# kugarem_nosilk.net
KiCad netlist of a schematic drawn in EAGLE
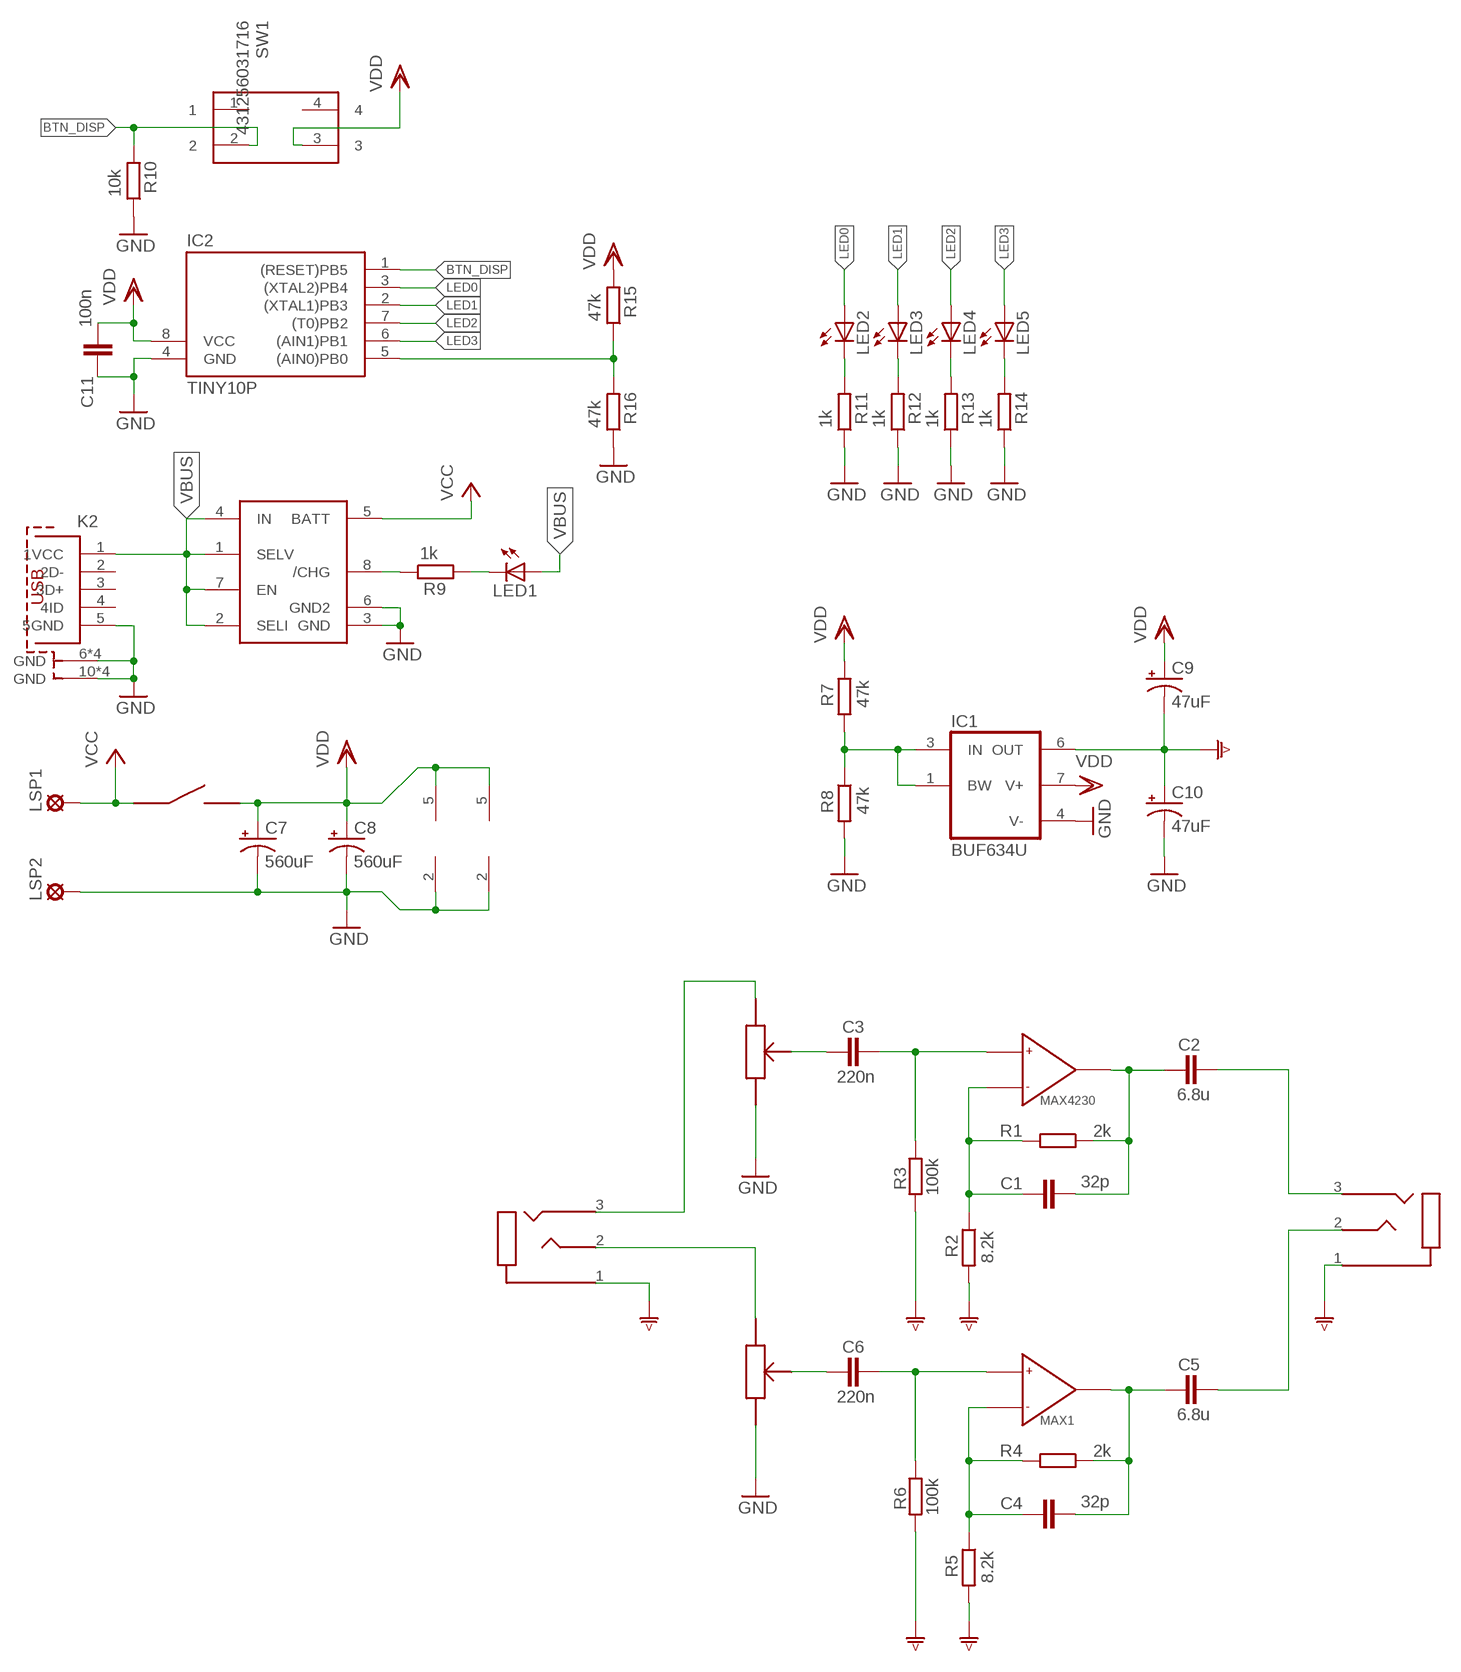
[diagram p0: schematic, sheet 1]

(export (version "E")
  (design (tool "Eeschema 10.0.6"))
  (components
    (comp (ref "C1")
      (value "32p")
      (footprint "eagle-import:C1206")
      (libsource (lib "eagle-import") (part "C-EUC1206"))
    )
    (comp (ref "C2")
      (value "6.8u")
      (footprint "eagle-import:C1206")
      (libsource (lib "eagle-import") (part "C-EUC1206"))
    )
    (comp (ref "C3")
      (value "220n")
      (footprint "eagle-import:C1206")
      (libsource (lib "eagle-import") (part "C-EUC1206"))
    )
    (comp (ref "C4")
      (value "32p")
      (footprint "eagle-import:C1206")
      (libsource (lib "eagle-import") (part "C-EUC1206"))
    )
    (comp (ref "C5")
      (value "6.8u")
      (footprint "eagle-import:C1206")
      (libsource (lib "eagle-import") (part "C-EUC1206"))
    )
    (comp (ref "C6")
      (value "220n")
      (footprint "eagle-import:C1206")
      (libsource (lib "eagle-import") (part "C-EUC1206"))
    )
    (comp (ref "C7")
      (value "560uF")
      (footprint "eagle-import:PANASONIC_G")
      (libsource (lib "eagle-import") (part "560UF-PANASONIC_G-25V-20%"))
    )
    (comp (ref "C8")
      (value "560uF")
      (footprint "eagle-import:PANASONIC_G")
      (libsource (lib "eagle-import") (part "560UF-PANASONIC_G-25V-20%"))
    )
    (comp (ref "C9")
      (value "47uF")
      (footprint "eagle-import:PANASONIC_D")
      (libsource (lib "eagle-import") (part "47UF-POLAR-PANASONIC_D-35V-20%"))
    )
    (comp (ref "C10")
      (value "47uF")
      (footprint "eagle-import:PANASONIC_D")
      (libsource (lib "eagle-import") (part "47UF-POLAR-PANASONIC_D-35V-20%"))
    )
    (comp (ref "C11")
      (value "100n")
      (footprint "eagle-import:C1206")
      (libsource (lib "eagle-import") (part "C-EUC1206"))
    )
    (comp (ref "IC1")
      (value "BUF634U")
      (footprint "eagle-import:SO08")
      (fields (field (name "MF") "TEXAS INSTRUMENTS"))
      (libsource (lib "eagle-import") (part "BUF634U"))
    )
    (comp (ref "IC2")
      (value "TINY10P")
      (footprint "eagle-import:DIL08")
      (libsource (lib "eagle-import") (part "TINY10P"))
    )
    (comp (ref "K2")
      (value "629105150921")
      (footprint "eagle-import:629105150921")
      (libsource (lib "eagle-import") (part "629105150921"))
    )
    (comp (ref "LED1")
      (value "LEDCHIPLED_1206")
      (footprint "eagle-import:CHIPLED_1206")
      (libsource (lib "eagle-import") (part "LEDCHIPLED_1206"))
    )
    (comp (ref "LED2")
      (value "LEDCHIPLED_1206")
      (footprint "eagle-import:CHIPLED_1206")
      (libsource (lib "eagle-import") (part "LEDCHIPLED_1206"))
    )
    (comp (ref "LED3")
      (value "LEDCHIPLED_1206")
      (footprint "eagle-import:CHIPLED_1206")
      (libsource (lib "eagle-import") (part "LEDCHIPLED_1206"))
    )
    (comp (ref "LED4")
      (value "LEDCHIPLED_1206")
      (footprint "eagle-import:CHIPLED_1206")
      (libsource (lib "eagle-import") (part "LEDCHIPLED_1206"))
    )
    (comp (ref "LED5")
      (value "LEDCHIPLED_1206")
      (footprint "eagle-import:CHIPLED_1206")
      (libsource (lib "eagle-import") (part "LEDCHIPLED_1206"))
    )
    (comp (ref "LSP1")
      (value "LSP10")
      (footprint "eagle-import:LSP10")
      (libsource (lib "eagle-import") (part "LSP10"))
    )
    (comp (ref "LSP2")
      (value "LSP10")
      (footprint "eagle-import:LSP10")
      (libsource (lib "eagle-import") (part "LSP10"))
    )
    (comp (ref "MAX1")
      (value "MAX4230")
      (footprint "eagle-import:SOT23-5L")
      (libsource (lib "eagle-import") (part "MAX4230"))
    )
    (comp (ref "MAX4230")
      (value "MAX4230")
      (footprint "eagle-import:SOT23-5L")
      (libsource (lib "eagle-import") (part "MAX4230"))
    )
    (comp (ref "R1")
      (value "2k")
      (footprint "eagle-import:R1206")
      (libsource (lib "eagle-import") (part "R-EU_R1206"))
    )
    (comp (ref "R2")
      (value "8.2k")
      (footprint "eagle-import:R1206")
      (libsource (lib "eagle-import") (part "R-EU_R1206"))
    )
    (comp (ref "R3")
      (value "100k")
      (footprint "eagle-import:R1206")
      (libsource (lib "eagle-import") (part "R-EU_R1206"))
    )
    (comp (ref "R4")
      (value "2k")
      (footprint "eagle-import:R1206")
      (libsource (lib "eagle-import") (part "R-EU_R1206"))
    )
    (comp (ref "R5")
      (value "8.2k")
      (footprint "eagle-import:R1206")
      (libsource (lib "eagle-import") (part "R-EU_R1206"))
    )
    (comp (ref "R6")
      (value "100k")
      (footprint "eagle-import:R1206")
      (libsource (lib "eagle-import") (part "R-EU_R1206"))
    )
    (comp (ref "R7")
      (value "47k")
      (footprint "eagle-import:R1206")
      (libsource (lib "eagle-import") (part "R-EU_R1206"))
    )
    (comp (ref "R8")
      (value "47k")
      (footprint "eagle-import:R1206")
      (libsource (lib "eagle-import") (part "R-EU_R1206"))
    )
    (comp (ref "R9")
      (value "1k")
      (footprint "eagle-import:R1206")
      (libsource (lib "eagle-import") (part "R-EU_R1206"))
    )
    (comp (ref "R10")
      (value "10k")
      (footprint "eagle-import:R1206")
      (libsource (lib "eagle-import") (part "R-EU_R1206"))
    )
    (comp (ref "R11")
      (value "1k")
      (footprint "eagle-import:R1206")
      (libsource (lib "eagle-import") (part "R-EU_R1206"))
    )
    (comp (ref "R12")
      (value "1k")
      (footprint "eagle-import:R1206")
      (libsource (lib "eagle-import") (part "R-EU_R1206"))
    )
    (comp (ref "R13")
      (value "1k")
      (footprint "eagle-import:R1206")
      (libsource (lib "eagle-import") (part "R-EU_R1206"))
    )
    (comp (ref "R14")
      (value "1k")
      (footprint "eagle-import:R1206")
      (libsource (lib "eagle-import") (part "R-EU_R1206"))
    )
    (comp (ref "R15")
      (value "47k")
      (footprint "eagle-import:R1206")
      (libsource (lib "eagle-import") (part "R-EU_R1206"))
    )
    (comp (ref "R16")
      (value "47k")
      (footprint "eagle-import:R1206")
      (libsource (lib "eagle-import") (part "R-EU_R1206"))
    )
    (comp (ref "SW1")
      (value "431256031716")
      (footprint "eagle-import:431256031716")
      (libsource (lib "eagle-import") (part "431256031716"))
    )
    (comp (ref "U$1")
      (value "100k")
      (footprint "eagle-import:PTR902")
      (libsource (lib "eagle-import") (part "PTR90"))
    )
    (comp (ref "U$2")
      (value "SJ1-3515-SMT-TR")
      (footprint "eagle-import:STX-35332-3N-TR")
      (libsource (lib "eagle-import") (part "SJ1-3515-SMT-TR"))
    )
    (comp (ref "U$3")
      (value "SJ1-3515-SMT-TR")
      (footprint "eagle-import:STX-35332-3N-TR")
      (libsource (lib "eagle-import") (part "SJ1-3515-SMT-TR"))
    )
    (comp (ref "U$4")
      (value "MAX1811SO8")
      (footprint "eagle-import:SO08")
      (libsource (lib "eagle-import") (part "MAX1811SO8"))
    )
  )
  (nets
    (net (code "1") (name "BTN_DISP") (class "Default")
      (node (ref "IC2") (pin "1") (pinfunction "(RESET)PB5_1") (pintype "bidirectional"))
      (node (ref "R10") (pin "2") (pinfunction "2_2") (pintype "passive"))
      (node (ref "SW1") (pin "2") (pinfunction "2_2") (pintype "bidirectional"))
    )
    (net (code "2") (name "GND") (class "Default")
      (node (ref "C10") (pin "-") (pinfunction "-_-") (pintype "passive"))
      (node (ref "C11") (pin "1") (pinfunction "1_1") (pintype "passive"))
      (node (ref "C7") (pin "-") (pinfunction "-_-") (pintype "passive"))
      (node (ref "C8") (pin "-") (pinfunction "-_-") (pintype "passive"))
      (node (ref "IC1") (pin "4") (pinfunction "V-_4") (pintype "power_in"))
      (node (ref "IC2") (pin "4") (pinfunction "GND_4") (pintype "power_in"))
      (node (ref "K2") (pin "10") (pinfunction "GND_10") (pintype "bidirectional"))
      (node (ref "K2") (pin "11") (pinfunction "GND_11") (pintype "bidirectional"))
      (node (ref "K2") (pin "12") (pinfunction "GND_12") (pintype "bidirectional"))
      (node (ref "K2") (pin "13") (pinfunction "GND_13") (pintype "bidirectional"))
      (node (ref "K2") (pin "5") (pinfunction "5GND_5") (pintype "passive"))
      (node (ref "K2") (pin "6") (pinfunction "GND_6") (pintype "bidirectional"))
      (node (ref "K2") (pin "7") (pinfunction "GND_7") (pintype "bidirectional"))
      (node (ref "K2") (pin "8") (pinfunction "GND_8") (pintype "bidirectional"))
      (node (ref "K2") (pin "9") (pinfunction "GND_9") (pintype "bidirectional"))
      (node (ref "LSP2") (pin "MP") (pinfunction "MP_MP") (pintype "passive"))
      (node (ref "MAX1") (pin "2") (pinfunction "N_2") (pintype "bidirectional"))
      (node (ref "MAX4230") (pin "2") (pinfunction "N_2") (pintype "bidirectional"))
      (node (ref "R10") (pin "1") (pinfunction "1_1") (pintype "passive"))
      (node (ref "R11") (pin "1") (pinfunction "1_1") (pintype "passive"))
      (node (ref "R12") (pin "1") (pinfunction "1_1") (pintype "passive"))
      (node (ref "R13") (pin "1") (pinfunction "1_1") (pintype "passive"))
      (node (ref "R14") (pin "1") (pinfunction "1_1") (pintype "passive"))
      (node (ref "R16") (pin "1") (pinfunction "1_1") (pintype "passive"))
      (node (ref "R8") (pin "2") (pinfunction "2_2") (pintype "passive"))
      (node (ref "U$1") (pin "R13") (pinfunction "13_R13") (pintype "bidirectional"))
      (node (ref "U$1") (pin "R23") (pinfunction "13_R23") (pintype "bidirectional"))
      (node (ref "U$4") (pin "3") (pinfunction "GND_3") (pintype "bidirectional"))
      (node (ref "U$4") (pin "6") (pinfunction "GND2_6") (pintype "bidirectional"))
    )
    (net (code "3") (name "LED0") (class "Default")
      (node (ref "IC2") (pin "3") (pinfunction "(XTAL2)PB4_3") (pintype "bidirectional"))
      (node (ref "LED2") (pin "A") (pinfunction "A_A") (pintype "passive"))
    )
    (net (code "4") (name "LED1") (class "Default")
      (node (ref "IC2") (pin "2") (pinfunction "(XTAL1)PB3_2") (pintype "bidirectional"))
      (node (ref "LED3") (pin "A") (pinfunction "A_A") (pintype "passive"))
    )
    (net (code "5") (name "LED2") (class "Default")
      (node (ref "IC2") (pin "7") (pinfunction "(T0)PB2_7") (pintype "bidirectional"))
      (node (ref "LED4") (pin "A") (pinfunction "A_A") (pintype "passive"))
    )
    (net (code "6") (name "LED3") (class "Default")
      (node (ref "IC2") (pin "6") (pinfunction "(AIN1)PB1_6") (pintype "bidirectional"))
      (node (ref "LED5") (pin "A") (pinfunction "A_A") (pintype "passive"))
    )
    (net (code "7") (name "Net-(IC1-BW)") (class "Default")
      (node (ref "IC1") (pin "1") (pinfunction "BW_1") (pintype "passive"))
      (node (ref "IC1") (pin "3") (pinfunction "IN_3") (pintype "input"))
      (node (ref "R7") (pin "2") (pinfunction "2_2") (pintype "passive"))
      (node (ref "R8") (pin "1") (pinfunction "1_1") (pintype "passive"))
    )
    (net (code "8") (name "Net-(IC2-(AIN0)PB0)") (class "Default")
      (node (ref "IC2") (pin "5") (pinfunction "(AIN0)PB0_5") (pintype "bidirectional"))
      (node (ref "R15") (pin "1") (pinfunction "1_1") (pintype "passive"))
      (node (ref "R16") (pin "2") (pinfunction "2_2") (pintype "passive"))
    )
    (net (code "9") (name "Net-(LED1-PadC)") (class "Default")
      (node (ref "LED1") (pin "C") (pinfunction "C_C") (pintype "passive"))
      (node (ref "R9") (pin "2") (pinfunction "2_2") (pintype "passive"))
    )
    (net (code "10") (name "Net-(LED2-PadC)") (class "Default")
      (node (ref "LED2") (pin "C") (pinfunction "C_C") (pintype "passive"))
      (node (ref "R11") (pin "2") (pinfunction "2_2") (pintype "passive"))
    )
    (net (code "11") (name "Net-(LED3-PadC)") (class "Default")
      (node (ref "LED3") (pin "C") (pinfunction "C_C") (pintype "passive"))
      (node (ref "R12") (pin "2") (pinfunction "2_2") (pintype "passive"))
    )
    (net (code "12") (name "Net-(LED4-PadC)") (class "Default")
      (node (ref "LED4") (pin "C") (pinfunction "C_C") (pintype "passive"))
      (node (ref "R13") (pin "2") (pinfunction "2_2") (pintype "passive"))
    )
    (net (code "13") (name "Net-(LED5-PadC)") (class "Default")
      (node (ref "LED5") (pin "C") (pinfunction "C_C") (pintype "passive"))
      (node (ref "R14") (pin "2") (pinfunction "2_2") (pintype "passive"))
    )
    (net (code "14") (name "Net-(MAX1A-IN+)") (class "Default")
      (node (ref "C6") (pin "2") (pinfunction "2_2") (pintype "passive"))
      (node (ref "MAX1") (pin "1") (pinfunction "IN+_1") (pintype "bidirectional"))
      (node (ref "R6") (pin "1") (pinfunction "1_1") (pintype "passive"))
    )
    (net (code "15") (name "Net-(MAX1A-IN-)") (class "Default")
      (node (ref "C4") (pin "1") (pinfunction "1_1") (pintype "passive"))
      (node (ref "MAX1") (pin "3") (pinfunction "IN-_3") (pintype "bidirectional"))
      (node (ref "R4") (pin "2") (pinfunction "2_2") (pintype "passive"))
      (node (ref "R5") (pin "1") (pinfunction "1_1") (pintype "passive"))
    )
    (net (code "16") (name "Net-(MAX1A-OUT)") (class "Default")
      (node (ref "C4") (pin "2") (pinfunction "2_2") (pintype "passive"))
      (node (ref "C5") (pin "1") (pinfunction "1_1") (pintype "passive"))
      (node (ref "MAX1") (pin "4") (pinfunction "OUT_4") (pintype "bidirectional"))
      (node (ref "R4") (pin "1") (pinfunction "1_1") (pintype "passive"))
    )
    (net (code "17") (name "Net-(MAX4230A-IN+)") (class "Default")
      (node (ref "C3") (pin "2") (pinfunction "2_2") (pintype "passive"))
      (node (ref "MAX4230") (pin "1") (pinfunction "IN+_1") (pintype "bidirectional"))
      (node (ref "R3") (pin "1") (pinfunction "1_1") (pintype "passive"))
    )
    (net (code "18") (name "Net-(MAX4230A-IN-)") (class "Default")
      (node (ref "C1") (pin "1") (pinfunction "1_1") (pintype "passive"))
      (node (ref "MAX4230") (pin "3") (pinfunction "IN-_3") (pintype "bidirectional"))
      (node (ref "R1") (pin "2") (pinfunction "2_2") (pintype "passive"))
      (node (ref "R2") (pin "1") (pinfunction "1_1") (pintype "passive"))
    )
    (net (code "19") (name "Net-(MAX4230A-OUT)") (class "Default")
      (node (ref "C1") (pin "2") (pinfunction "2_2") (pintype "passive"))
      (node (ref "C2") (pin "1") (pinfunction "1_1") (pintype "passive"))
      (node (ref "MAX4230") (pin "4") (pinfunction "OUT_4") (pintype "bidirectional"))
      (node (ref "R1") (pin "1") (pinfunction "1_1") (pintype "passive"))
    )
    (net (code "20") (name "Net-(U$1A-11)") (class "Default")
      (node (ref "U$1") (pin "R11") (pinfunction "11_R11") (pintype "bidirectional"))
      (node (ref "U$2") (pin "2") (pinfunction "TIP_2") (pintype "bidirectional"))
    )
    (net (code "21") (name "Net-(U$1A-12)") (class "Default")
      (node (ref "C6") (pin "1") (pinfunction "1_1") (pintype "passive"))
      (node (ref "U$1") (pin "R12") (pinfunction "12_R12") (pintype "bidirectional"))
    )
    (net (code "22") (name "Net-(U$1B-11)") (class "Default")
      (node (ref "U$1") (pin "R21") (pinfunction "11_R21") (pintype "bidirectional"))
      (node (ref "U$2") (pin "3") (pinfunction "RING_3") (pintype "bidirectional"))
    )
    (net (code "23") (name "Net-(U$1B-12)") (class "Default")
      (node (ref "C3") (pin "1") (pinfunction "1_1") (pintype "passive"))
      (node (ref "U$1") (pin "R22") (pinfunction "12_R22") (pintype "bidirectional"))
    )
    (net (code "24") (name "Net-(U$3-RING)") (class "Default")
      (node (ref "C2") (pin "2") (pinfunction "2_2") (pintype "passive"))
      (node (ref "U$3") (pin "3") (pinfunction "RING_3") (pintype "bidirectional"))
    )
    (net (code "25") (name "Net-(U$3-TIP)") (class "Default")
      (node (ref "C5") (pin "2") (pinfunction "2_2") (pintype "passive"))
      (node (ref "U$3") (pin "2") (pinfunction "TIP_2") (pintype "bidirectional"))
    )
    (net (code "26") (name "Net-(U$4-{slash}CHG)") (class "Default")
      (node (ref "R9") (pin "1") (pinfunction "1_1") (pintype "passive"))
      (node (ref "U$4") (pin "8") (pinfunction "/CHG_8") (pintype "bidirectional"))
    )
    (net (code "27") (name "VBUS") (class "Default")
      (node (ref "K2") (pin "1") (pinfunction "1VCC_1") (pintype "passive"))
      (node (ref "LED1") (pin "A") (pinfunction "A_A") (pintype "passive"))
      (node (ref "U$4") (pin "1") (pinfunction "SELV_1") (pintype "bidirectional"))
      (node (ref "U$4") (pin "2") (pinfunction "SELI_2") (pintype "bidirectional"))
      (node (ref "U$4") (pin "4") (pinfunction "IN_4") (pintype "bidirectional"))
      (node (ref "U$4") (pin "7") (pinfunction "EN_7") (pintype "bidirectional"))
    )
    (net (code "28") (name "VCC") (class "Default")
      (node (ref "LSP1") (pin "MP") (pinfunction "MP_MP") (pintype "passive"))
      (node (ref "U$1") (pin "SW1") (pinfunction "11_SW1") (pintype "bidirectional"))
      (node (ref "U$4") (pin "5") (pinfunction "BATT_5") (pintype "bidirectional"))
    )
    (net (code "29") (name "VDD") (class "Default")
      (node (ref "C11") (pin "2") (pinfunction "2_2") (pintype "passive"))
      (node (ref "C7") (pin "+") (pinfunction "+_+") (pintype "passive"))
      (node (ref "C8") (pin "+") (pinfunction "+_+") (pintype "passive"))
      (node (ref "C9") (pin "+") (pinfunction "+_+") (pintype "passive"))
      (node (ref "IC1") (pin "7") (pinfunction "V+_7") (pintype "power_in"))
      (node (ref "IC2") (pin "8") (pinfunction "VCC_8") (pintype "power_in"))
      (node (ref "MAX1") (pin "5") (pinfunction "P_5") (pintype "bidirectional"))
      (node (ref "MAX4230") (pin "5") (pinfunction "P_5") (pintype "bidirectional"))
      (node (ref "R15") (pin "2") (pinfunction "2_2") (pintype "passive"))
      (node (ref "R7") (pin "1") (pinfunction "1_1") (pintype "passive"))
      (node (ref "SW1") (pin "3") (pinfunction "3_3") (pintype "bidirectional"))
      (node (ref "U$1") (pin "SW2") (pinfunction "12_SW2") (pintype "bidirectional"))
    )
    (net (code "30") (name "VGND") (class "Default")
      (node (ref "C10") (pin "+") (pinfunction "+_+") (pintype "passive"))
      (node (ref "C9") (pin "-") (pinfunction "-_-") (pintype "passive"))
      (node (ref "IC1") (pin "6") (pinfunction "OUT_6") (pintype "output"))
      (node (ref "R2") (pin "2") (pinfunction "2_2") (pintype "passive"))
      (node (ref "R3") (pin "2") (pinfunction "2_2") (pintype "passive"))
      (node (ref "R5") (pin "2") (pinfunction "2_2") (pintype "passive"))
      (node (ref "R6") (pin "2") (pinfunction "2_2") (pintype "passive"))
      (node (ref "U$2") (pin "1") (pinfunction "SLEEVE_1") (pintype "bidirectional"))
      (node (ref "U$3") (pin "1") (pinfunction "SLEEVE_1") (pintype "bidirectional"))
    )
    (net (code "31") (name "unconnected-(K2-2D--Pad2)") (class "Default")
      (node (ref "K2") (pin "2") (pinfunction "2D-_2") (pintype "passive"))
    )
    (net (code "32") (name "unconnected-(K2-3D+-Pad3)") (class "Default")
      (node (ref "K2") (pin "3") (pinfunction "3D+_3") (pintype "passive"))
    )
    (net (code "33") (name "unconnected-(K2-4ID-Pad4)") (class "Default")
      (node (ref "K2") (pin "4") (pinfunction "4ID_4") (pintype "passive"))
    )
    (net (code "34") (name "unconnected-(SW1-Pad1)") (class "Default")
      (node (ref "SW1") (pin "1") (pinfunction "1_1") (pintype "bidirectional"))
    )
    (net (code "35") (name "unconnected-(SW1-Pad4)") (class "Default")
      (node (ref "SW1") (pin "4") (pinfunction "4_4") (pintype "bidirectional"))
    )
  )
)
